# EIB_1xA79026-001_large_pins_v1_2.net
KiCad netlist of a schematic drawn in EAGLE
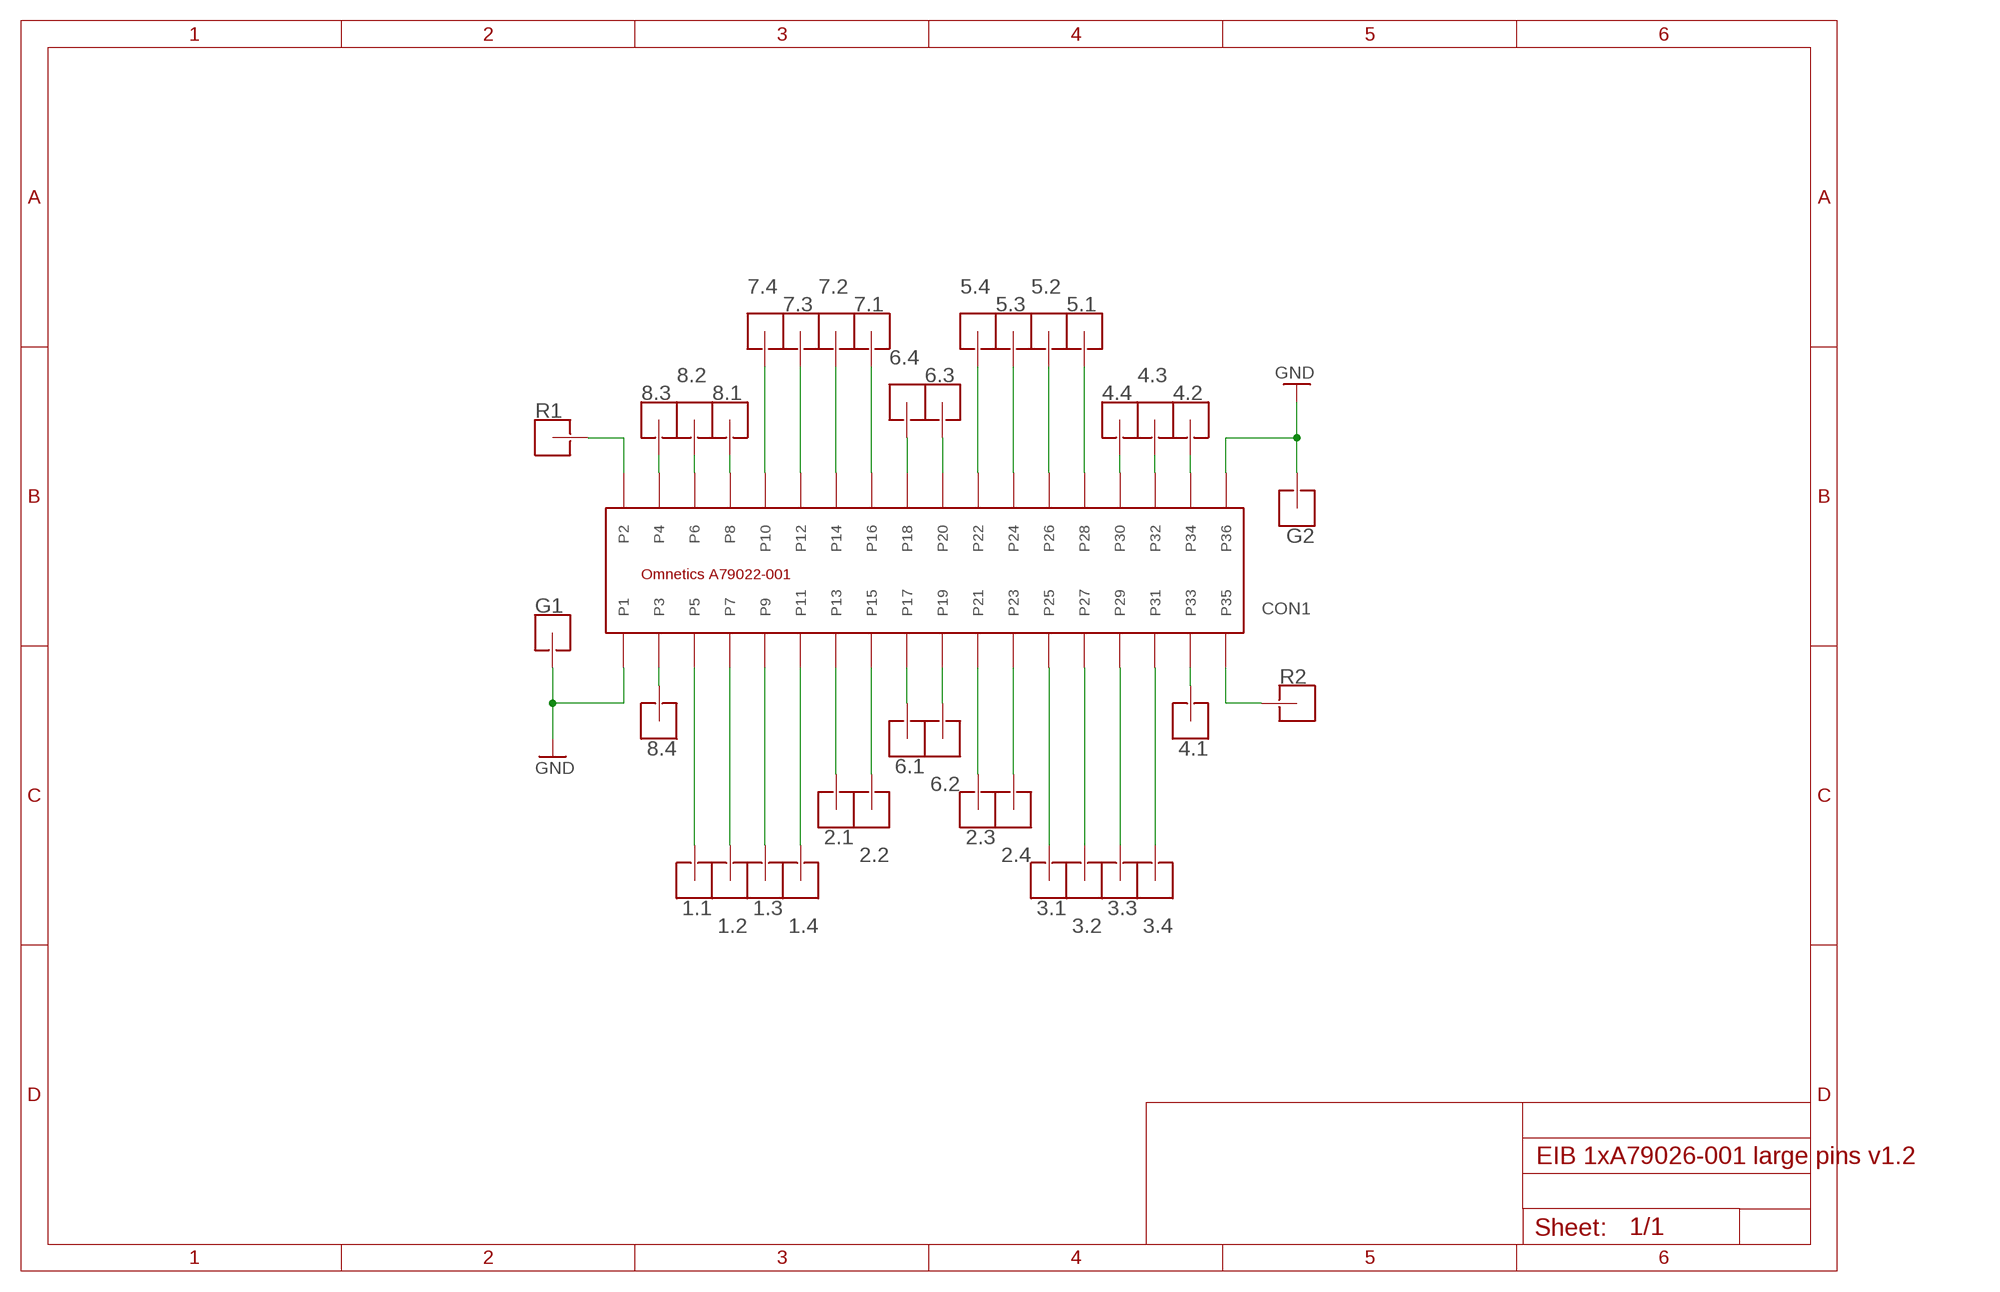
[diagram p0: schematic, sheet 1]

(export (version "E")
  (design (tool "Eeschema 10.0.6"))
  (components
    (comp (ref "1.1")
      (value "HOLE_L_G_PIN_V5")
      (footprint "eagle-import:LARGE_GOLD_PIN_V5")
      (libsource (lib "eagle-import") (part "HOLE_L_G_PIN_V5"))
    )
    (comp (ref "1.2")
      (value "HOLE_L_G_PIN_V5")
      (footprint "eagle-import:LARGE_GOLD_PIN_V5")
      (libsource (lib "eagle-import") (part "HOLE_L_G_PIN_V5"))
    )
    (comp (ref "1.3")
      (value "HOLE_L_G_PIN_V5")
      (footprint "eagle-import:LARGE_GOLD_PIN_V5")
      (libsource (lib "eagle-import") (part "HOLE_L_G_PIN_V5"))
    )
    (comp (ref "1.4")
      (value "HOLE_L_G_PIN_V5")
      (footprint "eagle-import:LARGE_GOLD_PIN_V5")
      (libsource (lib "eagle-import") (part "HOLE_L_G_PIN_V5"))
    )
    (comp (ref "2.1")
      (value "HOLE_L_G_PIN_V5")
      (footprint "eagle-import:LARGE_GOLD_PIN_V5")
      (libsource (lib "eagle-import") (part "HOLE_L_G_PIN_V5"))
    )
    (comp (ref "2.2")
      (value "HOLE_L_G_PIN_V5")
      (footprint "eagle-import:LARGE_GOLD_PIN_V5")
      (libsource (lib "eagle-import") (part "HOLE_L_G_PIN_V5"))
    )
    (comp (ref "2.3")
      (value "HOLE_L_G_PIN_V5")
      (footprint "eagle-import:LARGE_GOLD_PIN_V5")
      (libsource (lib "eagle-import") (part "HOLE_L_G_PIN_V5"))
    )
    (comp (ref "2.4")
      (value "HOLE_L_G_PIN_V5")
      (footprint "eagle-import:LARGE_GOLD_PIN_V5")
      (libsource (lib "eagle-import") (part "HOLE_L_G_PIN_V5"))
    )
    (comp (ref "3.1")
      (value "HOLE_L_G_PIN_V5")
      (footprint "eagle-import:LARGE_GOLD_PIN_V5")
      (libsource (lib "eagle-import") (part "HOLE_L_G_PIN_V5"))
    )
    (comp (ref "3.2")
      (value "HOLE_L_G_PIN_V5")
      (footprint "eagle-import:LARGE_GOLD_PIN_V5")
      (libsource (lib "eagle-import") (part "HOLE_L_G_PIN_V5"))
    )
    (comp (ref "3.3")
      (value "HOLE_L_G_PIN_V5")
      (footprint "eagle-import:LARGE_GOLD_PIN_V5")
      (libsource (lib "eagle-import") (part "HOLE_L_G_PIN_V5"))
    )
    (comp (ref "3.4")
      (value "HOLE_L_G_PIN_V5")
      (footprint "eagle-import:LARGE_GOLD_PIN_V5")
      (libsource (lib "eagle-import") (part "HOLE_L_G_PIN_V5"))
    )
    (comp (ref "4.1")
      (value "HOLE_L_G_PIN_V5")
      (footprint "eagle-import:LARGE_GOLD_PIN_V5")
      (libsource (lib "eagle-import") (part "HOLE_L_G_PIN_V5"))
    )
    (comp (ref "4.2")
      (value "HOLE_L_G_PIN_V5")
      (footprint "eagle-import:LARGE_GOLD_PIN_V5")
      (libsource (lib "eagle-import") (part "HOLE_L_G_PIN_V5"))
    )
    (comp (ref "4.3")
      (value "HOLE_L_G_PIN_V5")
      (footprint "eagle-import:LARGE_GOLD_PIN_V5")
      (libsource (lib "eagle-import") (part "HOLE_L_G_PIN_V5"))
    )
    (comp (ref "4.4")
      (value "HOLE_L_G_PIN_V5")
      (footprint "eagle-import:LARGE_GOLD_PIN_V5")
      (libsource (lib "eagle-import") (part "HOLE_L_G_PIN_V5"))
    )
    (comp (ref "5.1")
      (value "HOLE_L_G_PIN_V5")
      (footprint "eagle-import:LARGE_GOLD_PIN_V5")
      (libsource (lib "eagle-import") (part "HOLE_L_G_PIN_V5"))
    )
    (comp (ref "5.2")
      (value "HOLE_L_G_PIN_V5")
      (footprint "eagle-import:LARGE_GOLD_PIN_V5")
      (libsource (lib "eagle-import") (part "HOLE_L_G_PIN_V5"))
    )
    (comp (ref "5.3")
      (value "HOLE_L_G_PIN_V5")
      (footprint "eagle-import:LARGE_GOLD_PIN_V5")
      (libsource (lib "eagle-import") (part "HOLE_L_G_PIN_V5"))
    )
    (comp (ref "5.4")
      (value "HOLE_L_G_PIN_V5")
      (footprint "eagle-import:LARGE_GOLD_PIN_V5")
      (libsource (lib "eagle-import") (part "HOLE_L_G_PIN_V5"))
    )
    (comp (ref "6.1")
      (value "HOLE_L_G_PIN_V5")
      (footprint "eagle-import:LARGE_GOLD_PIN_V5")
      (libsource (lib "eagle-import") (part "HOLE_L_G_PIN_V5"))
    )
    (comp (ref "6.2")
      (value "HOLE_L_G_PIN_V5")
      (footprint "eagle-import:LARGE_GOLD_PIN_V5")
      (libsource (lib "eagle-import") (part "HOLE_L_G_PIN_V5"))
    )
    (comp (ref "6.3")
      (value "HOLE_L_G_PIN_V5")
      (footprint "eagle-import:LARGE_GOLD_PIN_V5")
      (libsource (lib "eagle-import") (part "HOLE_L_G_PIN_V5"))
    )
    (comp (ref "6.4")
      (value "HOLE_L_G_PIN_V5")
      (footprint "eagle-import:LARGE_GOLD_PIN_V5")
      (libsource (lib "eagle-import") (part "HOLE_L_G_PIN_V5"))
    )
    (comp (ref "7.1")
      (value "HOLE_L_G_PIN_V5")
      (footprint "eagle-import:LARGE_GOLD_PIN_V5")
      (libsource (lib "eagle-import") (part "HOLE_L_G_PIN_V5"))
    )
    (comp (ref "7.2")
      (value "HOLE_L_G_PIN_V5")
      (footprint "eagle-import:LARGE_GOLD_PIN_V5")
      (libsource (lib "eagle-import") (part "HOLE_L_G_PIN_V5"))
    )
    (comp (ref "7.3")
      (value "HOLE_L_G_PIN_V5")
      (footprint "eagle-import:LARGE_GOLD_PIN_V5")
      (libsource (lib "eagle-import") (part "HOLE_L_G_PIN_V5"))
    )
    (comp (ref "7.4")
      (value "HOLE_L_G_PIN_V5")
      (footprint "eagle-import:LARGE_GOLD_PIN_V5")
      (libsource (lib "eagle-import") (part "HOLE_L_G_PIN_V5"))
    )
    (comp (ref "8.1")
      (value "HOLE_L_G_PIN_V5")
      (footprint "eagle-import:LARGE_GOLD_PIN_V5")
      (libsource (lib "eagle-import") (part "HOLE_L_G_PIN_V5"))
    )
    (comp (ref "8.2")
      (value "HOLE_L_G_PIN_V5")
      (footprint "eagle-import:LARGE_GOLD_PIN_V5")
      (libsource (lib "eagle-import") (part "HOLE_L_G_PIN_V5"))
    )
    (comp (ref "8.3")
      (value "HOLE_L_G_PIN_V5")
      (footprint "eagle-import:LARGE_GOLD_PIN_V5")
      (libsource (lib "eagle-import") (part "HOLE_L_G_PIN_V5"))
    )
    (comp (ref "8.4")
      (value "HOLE_L_G_PIN_V5")
      (footprint "eagle-import:LARGE_GOLD_PIN_V5")
      (libsource (lib "eagle-import") (part "HOLE_L_G_PIN_V5"))
    )
    (comp (ref "CON1")
      (value "A79022-001_MALESMD")
      (footprint "eagle-import:A79026-001_MALE")
      (libsource (lib "eagle-import") (part "A79022-001_MALESMD"))
    )
    (comp (ref "G1")
      (value "HOLE_L_G_PIN_V5")
      (footprint "eagle-import:LARGE_GOLD_PIN_V5")
      (libsource (lib "eagle-import") (part "HOLE_L_G_PIN_V5"))
    )
    (comp (ref "G2")
      (value "HOLE_L_G_PIN_V5")
      (footprint "eagle-import:LARGE_GOLD_PIN_V5")
      (libsource (lib "eagle-import") (part "HOLE_L_G_PIN_V5"))
    )
    (comp (ref "R1")
      (value "HOLE_L_G_PIN_V5")
      (footprint "eagle-import:LARGE_GOLD_PIN_V5")
      (libsource (lib "eagle-import") (part "HOLE_L_G_PIN_V5"))
    )
    (comp (ref "R2")
      (value "HOLE_L_G_PIN_V5")
      (footprint "eagle-import:LARGE_GOLD_PIN_V5")
      (libsource (lib "eagle-import") (part "HOLE_L_G_PIN_V5"))
    )
  )
  (nets
    (net (code "1") (name "GND") (class "Default")
      (node (ref "CON1") (pin "P1") (pinfunction "P1_P1") (pintype "bidirectional"))
      (node (ref "CON1") (pin "P36") (pinfunction "P36_P36") (pintype "bidirectional"))
      (node (ref "G1") (pin "P$1") (pinfunction "P$1_P$1") (pintype "bidirectional"))
      (node (ref "G2") (pin "P$1") (pinfunction "P$1_P$1") (pintype "bidirectional"))
    )
    (net (code "2") (name "Net-(1.1-PadP$1)") (class "Default")
      (node (ref "1.1") (pin "P$1") (pinfunction "P$1_P$1") (pintype "bidirectional"))
      (node (ref "CON1") (pin "P5") (pinfunction "P5_P5") (pintype "bidirectional"))
    )
    (net (code "3") (name "Net-(1.2-PadP$1)") (class "Default")
      (node (ref "1.2") (pin "P$1") (pinfunction "P$1_P$1") (pintype "bidirectional"))
      (node (ref "CON1") (pin "P7") (pinfunction "P7_P7") (pintype "bidirectional"))
    )
    (net (code "4") (name "Net-(1.3-PadP$1)") (class "Default")
      (node (ref "1.3") (pin "P$1") (pinfunction "P$1_P$1") (pintype "bidirectional"))
      (node (ref "CON1") (pin "P9") (pinfunction "P9_P9") (pintype "bidirectional"))
    )
    (net (code "5") (name "Net-(1.4-PadP$1)") (class "Default")
      (node (ref "1.4") (pin "P$1") (pinfunction "P$1_P$1") (pintype "bidirectional"))
      (node (ref "CON1") (pin "P11") (pinfunction "P11_P11") (pintype "bidirectional"))
    )
    (net (code "6") (name "Net-(2.1-PadP$1)") (class "Default")
      (node (ref "2.1") (pin "P$1") (pinfunction "P$1_P$1") (pintype "bidirectional"))
      (node (ref "CON1") (pin "P13") (pinfunction "P13_P13") (pintype "bidirectional"))
    )
    (net (code "7") (name "Net-(2.2-PadP$1)") (class "Default")
      (node (ref "2.2") (pin "P$1") (pinfunction "P$1_P$1") (pintype "bidirectional"))
      (node (ref "CON1") (pin "P15") (pinfunction "P15_P15") (pintype "bidirectional"))
    )
    (net (code "8") (name "Net-(2.3-PadP$1)") (class "Default")
      (node (ref "2.3") (pin "P$1") (pinfunction "P$1_P$1") (pintype "bidirectional"))
      (node (ref "CON1") (pin "P21") (pinfunction "P21_P21") (pintype "bidirectional"))
    )
    (net (code "9") (name "Net-(2.4-PadP$1)") (class "Default")
      (node (ref "2.4") (pin "P$1") (pinfunction "P$1_P$1") (pintype "bidirectional"))
      (node (ref "CON1") (pin "P23") (pinfunction "P23_P23") (pintype "bidirectional"))
    )
    (net (code "10") (name "Net-(3.1-PadP$1)") (class "Default")
      (node (ref "3.1") (pin "P$1") (pinfunction "P$1_P$1") (pintype "bidirectional"))
      (node (ref "CON1") (pin "P25") (pinfunction "P25_P25") (pintype "bidirectional"))
    )
    (net (code "11") (name "Net-(3.2-PadP$1)") (class "Default")
      (node (ref "3.2") (pin "P$1") (pinfunction "P$1_P$1") (pintype "bidirectional"))
      (node (ref "CON1") (pin "P27") (pinfunction "P27_P27") (pintype "bidirectional"))
    )
    (net (code "12") (name "Net-(3.3-PadP$1)") (class "Default")
      (node (ref "3.3") (pin "P$1") (pinfunction "P$1_P$1") (pintype "bidirectional"))
      (node (ref "CON1") (pin "P29") (pinfunction "P29_P29") (pintype "bidirectional"))
    )
    (net (code "13") (name "Net-(3.4-PadP$1)") (class "Default")
      (node (ref "3.4") (pin "P$1") (pinfunction "P$1_P$1") (pintype "bidirectional"))
      (node (ref "CON1") (pin "P31") (pinfunction "P31_P31") (pintype "bidirectional"))
    )
    (net (code "14") (name "Net-(4.1-PadP$1)") (class "Default")
      (node (ref "4.1") (pin "P$1") (pinfunction "P$1_P$1") (pintype "bidirectional"))
      (node (ref "CON1") (pin "P33") (pinfunction "P33_P33") (pintype "bidirectional"))
    )
    (net (code "15") (name "Net-(4.2-PadP$1)") (class "Default")
      (node (ref "4.2") (pin "P$1") (pinfunction "P$1_P$1") (pintype "bidirectional"))
      (node (ref "CON1") (pin "P34") (pinfunction "P34_P34") (pintype "bidirectional"))
    )
    (net (code "16") (name "Net-(4.3-PadP$1)") (class "Default")
      (node (ref "4.3") (pin "P$1") (pinfunction "P$1_P$1") (pintype "bidirectional"))
      (node (ref "CON1") (pin "P32") (pinfunction "P32_P32") (pintype "bidirectional"))
    )
    (net (code "17") (name "Net-(4.4-PadP$1)") (class "Default")
      (node (ref "4.4") (pin "P$1") (pinfunction "P$1_P$1") (pintype "bidirectional"))
      (node (ref "CON1") (pin "P30") (pinfunction "P30_P30") (pintype "bidirectional"))
    )
    (net (code "18") (name "Net-(5.1-PadP$1)") (class "Default")
      (node (ref "5.1") (pin "P$1") (pinfunction "P$1_P$1") (pintype "bidirectional"))
      (node (ref "CON1") (pin "P28") (pinfunction "P28_P28") (pintype "bidirectional"))
    )
    (net (code "19") (name "Net-(5.2-PadP$1)") (class "Default")
      (node (ref "5.2") (pin "P$1") (pinfunction "P$1_P$1") (pintype "bidirectional"))
      (node (ref "CON1") (pin "P26") (pinfunction "P26_P26") (pintype "bidirectional"))
    )
    (net (code "20") (name "Net-(5.3-PadP$1)") (class "Default")
      (node (ref "5.3") (pin "P$1") (pinfunction "P$1_P$1") (pintype "bidirectional"))
      (node (ref "CON1") (pin "P24") (pinfunction "P24_P24") (pintype "bidirectional"))
    )
    (net (code "21") (name "Net-(5.4-PadP$1)") (class "Default")
      (node (ref "5.4") (pin "P$1") (pinfunction "P$1_P$1") (pintype "bidirectional"))
      (node (ref "CON1") (pin "P22") (pinfunction "P22_P22") (pintype "bidirectional"))
    )
    (net (code "22") (name "Net-(6.1-PadP$1)") (class "Default")
      (node (ref "6.1") (pin "P$1") (pinfunction "P$1_P$1") (pintype "bidirectional"))
      (node (ref "CON1") (pin "P17") (pinfunction "P17_P17") (pintype "bidirectional"))
    )
    (net (code "23") (name "Net-(6.2-PadP$1)") (class "Default")
      (node (ref "6.2") (pin "P$1") (pinfunction "P$1_P$1") (pintype "bidirectional"))
      (node (ref "CON1") (pin "P19") (pinfunction "P19_P19") (pintype "bidirectional"))
    )
    (net (code "24") (name "Net-(6.3-PadP$1)") (class "Default")
      (node (ref "6.3") (pin "P$1") (pinfunction "P$1_P$1") (pintype "bidirectional"))
      (node (ref "CON1") (pin "P20") (pinfunction "P20_P20") (pintype "bidirectional"))
    )
    (net (code "25") (name "Net-(6.4-PadP$1)") (class "Default")
      (node (ref "6.4") (pin "P$1") (pinfunction "P$1_P$1") (pintype "bidirectional"))
      (node (ref "CON1") (pin "P18") (pinfunction "P18_P18") (pintype "bidirectional"))
    )
    (net (code "26") (name "Net-(7.1-PadP$1)") (class "Default")
      (node (ref "7.1") (pin "P$1") (pinfunction "P$1_P$1") (pintype "bidirectional"))
      (node (ref "CON1") (pin "P16") (pinfunction "P16_P16") (pintype "bidirectional"))
    )
    (net (code "27") (name "Net-(7.2-PadP$1)") (class "Default")
      (node (ref "7.2") (pin "P$1") (pinfunction "P$1_P$1") (pintype "bidirectional"))
      (node (ref "CON1") (pin "P14") (pinfunction "P14_P14") (pintype "bidirectional"))
    )
    (net (code "28") (name "Net-(7.3-PadP$1)") (class "Default")
      (node (ref "7.3") (pin "P$1") (pinfunction "P$1_P$1") (pintype "bidirectional"))
      (node (ref "CON1") (pin "P12") (pinfunction "P12_P12") (pintype "bidirectional"))
    )
    (net (code "29") (name "Net-(7.4-PadP$1)") (class "Default")
      (node (ref "7.4") (pin "P$1") (pinfunction "P$1_P$1") (pintype "bidirectional"))
      (node (ref "CON1") (pin "P10") (pinfunction "P10_P10") (pintype "bidirectional"))
    )
    (net (code "30") (name "Net-(8.1-PadP$1)") (class "Default")
      (node (ref "8.1") (pin "P$1") (pinfunction "P$1_P$1") (pintype "bidirectional"))
      (node (ref "CON1") (pin "P8") (pinfunction "P8_P8") (pintype "bidirectional"))
    )
    (net (code "31") (name "Net-(8.2-PadP$1)") (class "Default")
      (node (ref "8.2") (pin "P$1") (pinfunction "P$1_P$1") (pintype "bidirectional"))
      (node (ref "CON1") (pin "P6") (pinfunction "P6_P6") (pintype "bidirectional"))
    )
    (net (code "32") (name "Net-(8.3-PadP$1)") (class "Default")
      (node (ref "8.3") (pin "P$1") (pinfunction "P$1_P$1") (pintype "bidirectional"))
      (node (ref "CON1") (pin "P4") (pinfunction "P4_P4") (pintype "bidirectional"))
    )
    (net (code "33") (name "Net-(8.4-PadP$1)") (class "Default")
      (node (ref "8.4") (pin "P$1") (pinfunction "P$1_P$1") (pintype "bidirectional"))
      (node (ref "CON1") (pin "P3") (pinfunction "P3_P3") (pintype "bidirectional"))
    )
    (net (code "34") (name "Net-(CON1-PadP2)") (class "Default")
      (node (ref "CON1") (pin "P2") (pinfunction "P2_P2") (pintype "bidirectional"))
      (node (ref "R1") (pin "P$1") (pinfunction "P$1_P$1") (pintype "bidirectional"))
    )
    (net (code "35") (name "Net-(CON1-PadP35)") (class "Default")
      (node (ref "CON1") (pin "P35") (pinfunction "P35_P35") (pintype "bidirectional"))
      (node (ref "R2") (pin "P$1") (pinfunction "P$1_P$1") (pintype "bidirectional"))
    )
  )
)
